# Shield_r0.net
KiCad netlist of a schematic drawn in EAGLE
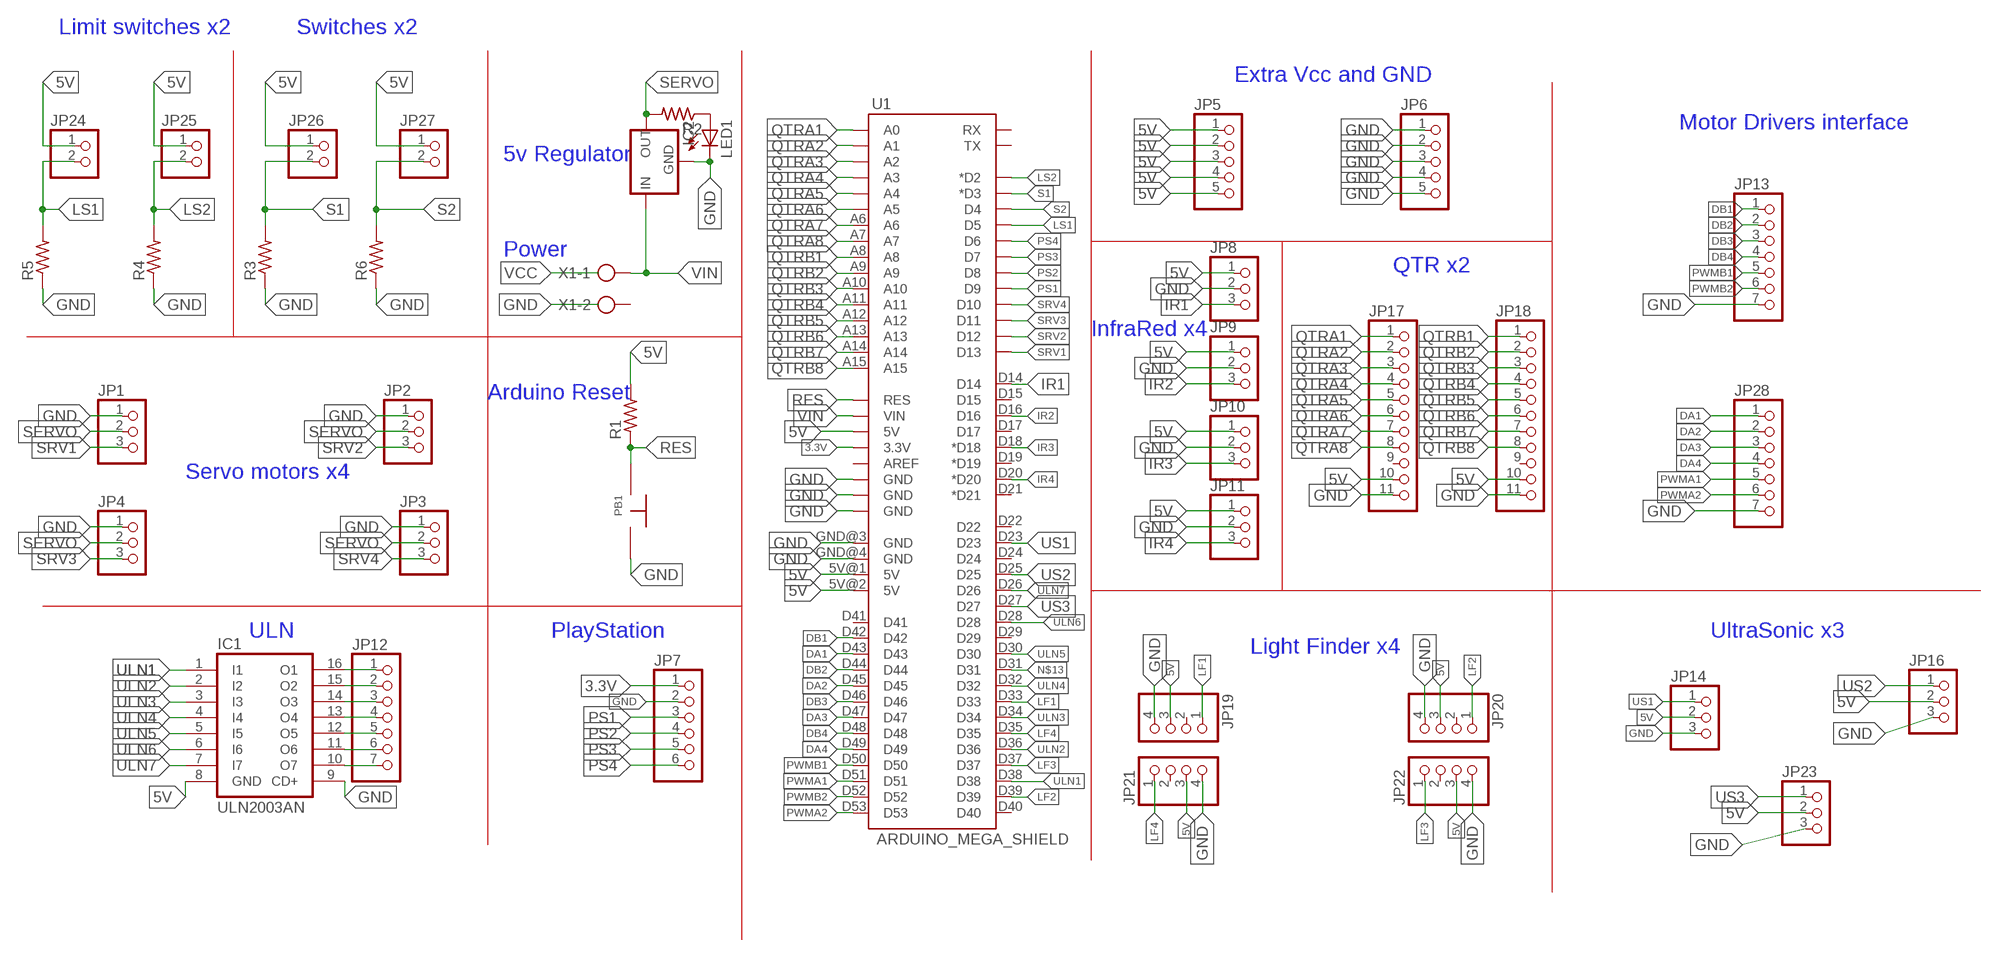
[diagram p0: schematic, sheet 1]

(export (version "E")
  (design (tool "Eeschema 10.0.6"))
  (components
    (comp (ref "IC1")
      (value "ULN2003AN")
      (footprint "eagle-import:DIL16")
      (libsource (lib "eagle-import") (part "ULN2003AN"))
    )
    (comp (ref "IC2")
      (value "78XXS")
      (footprint "eagle-import:78XXS")
      (libsource (lib "eagle-import") (part "78XXS"))
    )
    (comp (ref "JP1")
      (value "PINHD-1X3")
      (footprint "eagle-import:1X03")
      (libsource (lib "eagle-import") (part "PINHD-1X3"))
    )
    (comp (ref "JP2")
      (value "PINHD-1X3")
      (footprint "eagle-import:1X03")
      (libsource (lib "eagle-import") (part "PINHD-1X3"))
    )
    (comp (ref "JP3")
      (value "PINHD-1X3")
      (footprint "eagle-import:1X03")
      (libsource (lib "eagle-import") (part "PINHD-1X3"))
    )
    (comp (ref "JP4")
      (value "PINHD-1X3")
      (footprint "eagle-import:1X03")
      (libsource (lib "eagle-import") (part "PINHD-1X3"))
    )
    (comp (ref "JP5")
      (value "PINHD-1X5")
      (footprint "eagle-import:1X05")
      (libsource (lib "eagle-import") (part "PINHD-1X5"))
    )
    (comp (ref "JP6")
      (value "PINHD-1X5")
      (footprint "eagle-import:1X05")
      (libsource (lib "eagle-import") (part "PINHD-1X5"))
    )
    (comp (ref "JP7")
      (value "PINHD-1X6")
      (footprint "eagle-import:1X06")
      (libsource (lib "eagle-import") (part "PINHD-1X6"))
    )
    (comp (ref "JP8")
      (value "PINHD-1X3")
      (footprint "eagle-import:1X03")
      (libsource (lib "eagle-import") (part "PINHD-1X3"))
    )
    (comp (ref "JP9")
      (value "PINHD-1X3")
      (footprint "eagle-import:1X03")
      (libsource (lib "eagle-import") (part "PINHD-1X3"))
    )
    (comp (ref "JP10")
      (value "PINHD-1X3")
      (footprint "eagle-import:1X03")
      (libsource (lib "eagle-import") (part "PINHD-1X3"))
    )
    (comp (ref "JP11")
      (value "PINHD-1X3")
      (footprint "eagle-import:1X03")
      (libsource (lib "eagle-import") (part "PINHD-1X3"))
    )
    (comp (ref "JP12")
      (value "PINHD-1X7")
      (footprint "eagle-import:1X07")
      (libsource (lib "eagle-import") (part "PINHD-1X7"))
    )
    (comp (ref "JP13")
      (value "PINHD-1X7")
      (footprint "eagle-import:1X07")
      (libsource (lib "eagle-import") (part "PINHD-1X7"))
    )
    (comp (ref "JP14")
      (value "PINHD-1X3")
      (footprint "eagle-import:1X03")
      (libsource (lib "eagle-import") (part "PINHD-1X3"))
    )
    (comp (ref "JP16")
      (value "PINHD-1X3")
      (footprint "eagle-import:1X03")
      (libsource (lib "eagle-import") (part "PINHD-1X3"))
    )
    (comp (ref "JP17")
      (value "PINHD-1X11")
      (footprint "eagle-import:1X11")
      (libsource (lib "eagle-import") (part "PINHD-1X11"))
    )
    (comp (ref "JP18")
      (value "PINHD-1X11")
      (footprint "eagle-import:1X11")
      (libsource (lib "eagle-import") (part "PINHD-1X11"))
    )
    (comp (ref "JP19")
      (value "PINHD-1X4")
      (footprint "eagle-import:1X04")
      (libsource (lib "eagle-import") (part "PINHD-1X4"))
    )
    (comp (ref "JP20")
      (value "PINHD-1X4")
      (footprint "eagle-import:1X04")
      (libsource (lib "eagle-import") (part "PINHD-1X4"))
    )
    (comp (ref "JP21")
      (value "PINHD-1X4")
      (footprint "eagle-import:1X04")
      (libsource (lib "eagle-import") (part "PINHD-1X4"))
    )
    (comp (ref "JP22")
      (value "PINHD-1X4")
      (footprint "eagle-import:1X04")
      (libsource (lib "eagle-import") (part "PINHD-1X4"))
    )
    (comp (ref "JP23")
      (value "PINHD-1X3")
      (footprint "eagle-import:1X03")
      (libsource (lib "eagle-import") (part "PINHD-1X3"))
    )
    (comp (ref "JP24")
      (value "PINHD-1X2")
      (footprint "eagle-import:1X02")
      (libsource (lib "eagle-import") (part "PINHD-1X2"))
    )
    (comp (ref "JP25")
      (value "PINHD-1X2")
      (footprint "eagle-import:1X02")
      (libsource (lib "eagle-import") (part "PINHD-1X2"))
    )
    (comp (ref "JP26")
      (value "PINHD-1X2")
      (footprint "eagle-import:1X02")
      (libsource (lib "eagle-import") (part "PINHD-1X2"))
    )
    (comp (ref "JP27")
      (value "PINHD-1X2")
      (footprint "eagle-import:1X02")
      (libsource (lib "eagle-import") (part "PINHD-1X2"))
    )
    (comp (ref "JP28")
      (value "PINHD-1X7")
      (footprint "eagle-import:1X07")
      (libsource (lib "eagle-import") (part "PINHD-1X7"))
    )
    (comp (ref "LED1")
      (value "LED5MM")
      (footprint "eagle-import:LED5MM")
      (libsource (lib "eagle-import") (part "LED5MM"))
    )
    (comp (ref "PB1")
      (value "PUSH")
      (footprint "eagle-import:PUSHBUTTON")
      (libsource (lib "eagle-import") (part "PUSH"))
    )
    (comp (ref "R1")
      (value "R-US_0207/10")
      (footprint "eagle-import:0207_10")
      (libsource (lib "eagle-import") (part "R-US_0207/10"))
    )
    (comp (ref "R2")
      (value "R-US_0207/10")
      (footprint "eagle-import:0207_10")
      (libsource (lib "eagle-import") (part "R-US_0207/10"))
    )
    (comp (ref "R3")
      (value "R-US_0207/10")
      (footprint "eagle-import:0207_10")
      (libsource (lib "eagle-import") (part "R-US_0207/10"))
    )
    (comp (ref "R4")
      (value "R-US_0207/10")
      (footprint "eagle-import:0207_10")
      (libsource (lib "eagle-import") (part "R-US_0207/10"))
    )
    (comp (ref "R5")
      (value "R-US_0207/10")
      (footprint "eagle-import:0207_10")
      (libsource (lib "eagle-import") (part "R-US_0207/10"))
    )
    (comp (ref "R6")
      (value "R-US_0207/10")
      (footprint "eagle-import:0207_10")
      (libsource (lib "eagle-import") (part "R-US_0207/10"))
    )
    (comp (ref "U1")
      (value "ARDUINO_MEGA_SHIELD")
      (footprint "eagle-import:ARDUINO_MEGA_SHIELD")
      (libsource (lib "eagle-import") (part "ARDUINO_MEGA_SHIELD"))
    )
    (comp (ref "X1")
      (value "AK500/2-H")
      (footprint "eagle-import:AK500_2-H")
      (libsource (lib "eagle-import") (part "AK500/2-H"))
    )
  )
  (nets
    (net (code "1") (name "3.3V") (class "Default")
      (node (ref "JP7") (pin "1") (pinfunction "1_1") (pintype "passive"))
      (node (ref "U1") (pin "3.3V") (pinfunction "3.3V_3.3V") (pintype "bidirectional"))
    )
    (net (code "2") (name "5V") (class "Default")
      (node (ref "IC1") (pin "8") (pinfunction "GND_8") (pintype "power_in"))
      (node (ref "JP10") (pin "1") (pinfunction "1_1") (pintype "passive"))
      (node (ref "JP11") (pin "1") (pinfunction "1_1") (pintype "passive"))
      (node (ref "JP14") (pin "2") (pinfunction "2_2") (pintype "passive"))
      (node (ref "JP16") (pin "2") (pinfunction "2_2") (pintype "passive"))
      (node (ref "JP17") (pin "10") (pinfunction "10_10") (pintype "passive"))
      (node (ref "JP18") (pin "10") (pinfunction "10_10") (pintype "passive"))
      (node (ref "JP19") (pin "3") (pinfunction "3_3") (pintype "passive"))
      (node (ref "JP20") (pin "3") (pinfunction "3_3") (pintype "passive"))
      (node (ref "JP21") (pin "3") (pinfunction "3_3") (pintype "passive"))
      (node (ref "JP22") (pin "3") (pinfunction "3_3") (pintype "passive"))
      (node (ref "JP23") (pin "2") (pinfunction "2_2") (pintype "passive"))
      (node (ref "JP24") (pin "1") (pinfunction "1_1") (pintype "passive"))
      (node (ref "JP25") (pin "1") (pinfunction "1_1") (pintype "passive"))
      (node (ref "JP26") (pin "1") (pinfunction "1_1") (pintype "passive"))
      (node (ref "JP27") (pin "1") (pinfunction "1_1") (pintype "passive"))
      (node (ref "JP5") (pin "1") (pinfunction "1_1") (pintype "passive"))
      (node (ref "JP5") (pin "2") (pinfunction "2_2") (pintype "passive"))
      (node (ref "JP5") (pin "3") (pinfunction "3_3") (pintype "passive"))
      (node (ref "JP5") (pin "4") (pinfunction "4_4") (pintype "passive"))
      (node (ref "JP5") (pin "5") (pinfunction "5_5") (pintype "passive"))
      (node (ref "JP8") (pin "1") (pinfunction "1_1") (pintype "passive"))
      (node (ref "JP9") (pin "1") (pinfunction "1_1") (pintype "passive"))
      (node (ref "R1") (pin "2") (pinfunction "2_2") (pintype "passive"))
      (node (ref "U1") (pin "5V@0") (pinfunction "5V_5V@0") (pintype "power_in"))
      (node (ref "U1") (pin "5V@1") (pinfunction "5V_5V@1") (pintype "power_in"))
      (node (ref "U1") (pin "5V@2") (pinfunction "5V_5V@2") (pintype "power_in"))
    )
    (net (code "3") (name "DA1") (class "Default")
      (node (ref "JP28") (pin "1") (pinfunction "1_1") (pintype "passive"))
      (node (ref "U1") (pin "D43") (pinfunction "D43_D43") (pintype "bidirectional"))
    )
    (net (code "4") (name "DA2") (class "Default")
      (node (ref "JP28") (pin "2") (pinfunction "2_2") (pintype "passive"))
      (node (ref "U1") (pin "D45") (pinfunction "D45_D45") (pintype "bidirectional"))
    )
    (net (code "5") (name "DA3") (class "Default")
      (node (ref "JP28") (pin "3") (pinfunction "3_3") (pintype "passive"))
      (node (ref "U1") (pin "D47") (pinfunction "D47_D47") (pintype "bidirectional"))
    )
    (net (code "6") (name "DA4") (class "Default")
      (node (ref "JP28") (pin "4") (pinfunction "4_4") (pintype "passive"))
      (node (ref "U1") (pin "D49") (pinfunction "D49_D49") (pintype "bidirectional"))
    )
    (net (code "7") (name "DB1") (class "Default")
      (node (ref "JP13") (pin "1") (pinfunction "1_1") (pintype "passive"))
      (node (ref "U1") (pin "D42") (pinfunction "D42_D42") (pintype "bidirectional"))
    )
    (net (code "8") (name "DB2") (class "Default")
      (node (ref "JP13") (pin "2") (pinfunction "2_2") (pintype "passive"))
      (node (ref "U1") (pin "D44") (pinfunction "D44_D44") (pintype "bidirectional"))
    )
    (net (code "9") (name "DB3") (class "Default")
      (node (ref "JP13") (pin "3") (pinfunction "3_3") (pintype "passive"))
      (node (ref "U1") (pin "D46") (pinfunction "D46_D46") (pintype "bidirectional"))
    )
    (net (code "10") (name "DB4") (class "Default")
      (node (ref "JP13") (pin "4") (pinfunction "4_4") (pintype "passive"))
      (node (ref "U1") (pin "D48") (pinfunction "D48_D48") (pintype "bidirectional"))
    )
    (net (code "11") (name "GND") (class "Default")
      (node (ref "IC1") (pin "9") (pinfunction "CD+_9") (pintype "passive"))
      (node (ref "IC2") (pin "GND") (pinfunction "GND_GND") (pintype "input"))
      (node (ref "JP1") (pin "1") (pinfunction "1_1") (pintype "passive"))
      (node (ref "JP10") (pin "2") (pinfunction "2_2") (pintype "passive"))
      (node (ref "JP11") (pin "2") (pinfunction "2_2") (pintype "passive"))
      (node (ref "JP13") (pin "7") (pinfunction "7_7") (pintype "passive"))
      (node (ref "JP14") (pin "3") (pinfunction "3_3") (pintype "passive"))
      (node (ref "JP16") (pin "3") (pinfunction "3_3") (pintype "passive"))
      (node (ref "JP17") (pin "11") (pinfunction "11_11") (pintype "passive"))
      (node (ref "JP18") (pin "11") (pinfunction "11_11") (pintype "passive"))
      (node (ref "JP19") (pin "4") (pinfunction "4_4") (pintype "passive"))
      (node (ref "JP2") (pin "1") (pinfunction "1_1") (pintype "passive"))
      (node (ref "JP20") (pin "4") (pinfunction "4_4") (pintype "passive"))
      (node (ref "JP21") (pin "4") (pinfunction "4_4") (pintype "passive"))
      (node (ref "JP22") (pin "4") (pinfunction "4_4") (pintype "passive"))
      (node (ref "JP23") (pin "3") (pinfunction "3_3") (pintype "passive"))
      (node (ref "JP28") (pin "7") (pinfunction "7_7") (pintype "passive"))
      (node (ref "JP3") (pin "1") (pinfunction "1_1") (pintype "passive"))
      (node (ref "JP4") (pin "1") (pinfunction "1_1") (pintype "passive"))
      (node (ref "JP6") (pin "1") (pinfunction "1_1") (pintype "passive"))
      (node (ref "JP6") (pin "2") (pinfunction "2_2") (pintype "passive"))
      (node (ref "JP6") (pin "3") (pinfunction "3_3") (pintype "passive"))
      (node (ref "JP6") (pin "4") (pinfunction "4_4") (pintype "passive"))
      (node (ref "JP6") (pin "5") (pinfunction "5_5") (pintype "passive"))
      (node (ref "JP7") (pin "2") (pinfunction "2_2") (pintype "passive"))
      (node (ref "JP8") (pin "2") (pinfunction "2_2") (pintype "passive"))
      (node (ref "JP9") (pin "2") (pinfunction "2_2") (pintype "passive"))
      (node (ref "LED1") (pin "K") (pinfunction "C_K") (pintype "passive"))
      (node (ref "PB1") (pin "P$2") (pinfunction "3_P$2") (pintype "bidirectional"))
      (node (ref "R3") (pin "1") (pinfunction "1_1") (pintype "passive"))
      (node (ref "R4") (pin "1") (pinfunction "1_1") (pintype "passive"))
      (node (ref "R5") (pin "1") (pinfunction "1_1") (pintype "passive"))
      (node (ref "R6") (pin "1") (pinfunction "1_1") (pintype "passive"))
      (node (ref "U1") (pin "GND@0") (pinfunction "GND_GND@0") (pintype "power_in"))
      (node (ref "U1") (pin "GND@1") (pinfunction "GND_GND@1") (pintype "power_in"))
      (node (ref "U1") (pin "GND@2") (pinfunction "GND_GND@2") (pintype "power_in"))
      (node (ref "U1") (pin "GND@3") (pinfunction "GND_GND@3") (pintype "power_in"))
      (node (ref "U1") (pin "GND@4") (pinfunction "GND_GND@4") (pintype "power_in"))
    )
    (net (code "12") (name "IR1") (class "Default")
      (node (ref "JP8") (pin "3") (pinfunction "3_3") (pintype "passive"))
      (node (ref "U1") (pin "D14") (pinfunction "D14_D14") (pintype "bidirectional"))
    )
    (net (code "13") (name "IR2") (class "Default")
      (node (ref "JP9") (pin "3") (pinfunction "3_3") (pintype "passive"))
      (node (ref "U1") (pin "D16") (pinfunction "D16_D16") (pintype "bidirectional"))
    )
    (net (code "14") (name "IR3") (class "Default")
      (node (ref "JP10") (pin "3") (pinfunction "3_3") (pintype "passive"))
      (node (ref "U1") (pin "D18") (pinfunction "*D18_D18") (pintype "bidirectional"))
    )
    (net (code "15") (name "IR4") (class "Default")
      (node (ref "JP11") (pin "3") (pinfunction "3_3") (pintype "passive"))
      (node (ref "U1") (pin "D20") (pinfunction "*D20_D20") (pintype "bidirectional"))
    )
    (net (code "16") (name "LF1") (class "Default")
      (node (ref "JP19") (pin "1") (pinfunction "1_1") (pintype "passive"))
      (node (ref "U1") (pin "D33") (pinfunction "D33_D33") (pintype "bidirectional"))
    )
    (net (code "17") (name "LF2") (class "Default")
      (node (ref "JP20") (pin "1") (pinfunction "1_1") (pintype "passive"))
      (node (ref "U1") (pin "D39") (pinfunction "D39_D39") (pintype "bidirectional"))
    )
    (net (code "18") (name "LF3") (class "Default")
      (node (ref "JP22") (pin "1") (pinfunction "1_1") (pintype "passive"))
      (node (ref "U1") (pin "D37") (pinfunction "D37_D37") (pintype "bidirectional"))
    )
    (net (code "19") (name "LF4") (class "Default")
      (node (ref "JP21") (pin "1") (pinfunction "1_1") (pintype "passive"))
      (node (ref "U1") (pin "D35") (pinfunction "D35_D35") (pintype "bidirectional"))
    )
    (net (code "20") (name "LS1") (class "Default")
      (node (ref "JP24") (pin "2") (pinfunction "2_2") (pintype "passive"))
      (node (ref "R5") (pin "2") (pinfunction "2_2") (pintype "passive"))
      (node (ref "U1") (pin "D5") (pinfunction "D5_D5") (pintype "bidirectional"))
    )
    (net (code "21") (name "LS2") (class "Default")
      (node (ref "JP25") (pin "2") (pinfunction "2_2") (pintype "passive"))
      (node (ref "R4") (pin "2") (pinfunction "2_2") (pintype "passive"))
      (node (ref "U1") (pin "D2") (pinfunction "*D2_D2") (pintype "bidirectional"))
    )
    (net (code "22") (name "N$13") (class "Default")
      (node (ref "U1") (pin "D31") (pinfunction "D31_D31") (pintype "bidirectional"))
    )
    (net (code "23") (name "Net-(IC1-O1)") (class "Default")
      (node (ref "IC1") (pin "16") (pinfunction "O1_16") (pintype "open_collector"))
      (node (ref "JP12") (pin "1") (pinfunction "1_1") (pintype "passive"))
    )
    (net (code "24") (name "Net-(IC1-O2)") (class "Default")
      (node (ref "IC1") (pin "15") (pinfunction "O2_15") (pintype "open_collector"))
      (node (ref "JP12") (pin "2") (pinfunction "2_2") (pintype "passive"))
    )
    (net (code "25") (name "Net-(IC1-O3)") (class "Default")
      (node (ref "IC1") (pin "14") (pinfunction "O3_14") (pintype "open_collector"))
      (node (ref "JP12") (pin "3") (pinfunction "3_3") (pintype "passive"))
    )
    (net (code "26") (name "Net-(IC1-O4)") (class "Default")
      (node (ref "IC1") (pin "13") (pinfunction "O4_13") (pintype "open_collector"))
      (node (ref "JP12") (pin "4") (pinfunction "4_4") (pintype "passive"))
    )
    (net (code "27") (name "Net-(IC1-O5)") (class "Default")
      (node (ref "IC1") (pin "12") (pinfunction "O5_12") (pintype "open_collector"))
      (node (ref "JP12") (pin "5") (pinfunction "5_5") (pintype "passive"))
    )
    (net (code "28") (name "Net-(IC1-O6)") (class "Default")
      (node (ref "IC1") (pin "11") (pinfunction "O6_11") (pintype "open_collector"))
      (node (ref "JP12") (pin "6") (pinfunction "6_6") (pintype "passive"))
    )
    (net (code "29") (name "Net-(IC1-O7)") (class "Default")
      (node (ref "IC1") (pin "10") (pinfunction "O7_10") (pintype "open_collector"))
      (node (ref "JP12") (pin "7") (pinfunction "7_7") (pintype "passive"))
    )
    (net (code "30") (name "Net-(LED1-PadA)") (class "Default")
      (node (ref "LED1") (pin "A") (pinfunction "A_A") (pintype "passive"))
      (node (ref "R2") (pin "1") (pinfunction "1_1") (pintype "passive"))
    )
    (net (code "31") (name "PS1") (class "Default")
      (node (ref "JP7") (pin "3") (pinfunction "3_3") (pintype "passive"))
      (node (ref "U1") (pin "D9") (pinfunction "D9_D9") (pintype "bidirectional"))
    )
    (net (code "32") (name "PS2") (class "Default")
      (node (ref "JP7") (pin "4") (pinfunction "4_4") (pintype "passive"))
      (node (ref "U1") (pin "D8") (pinfunction "D8_D8") (pintype "bidirectional"))
    )
    (net (code "33") (name "PS3") (class "Default")
      (node (ref "JP7") (pin "5") (pinfunction "5_5") (pintype "passive"))
      (node (ref "U1") (pin "D7") (pinfunction "D7_D7") (pintype "bidirectional"))
    )
    (net (code "34") (name "PS4") (class "Default")
      (node (ref "JP7") (pin "6") (pinfunction "6_6") (pintype "passive"))
      (node (ref "U1") (pin "D6") (pinfunction "D6_D6") (pintype "bidirectional"))
    )
    (net (code "35") (name "PWMA1") (class "Default")
      (node (ref "JP28") (pin "5") (pinfunction "5_5") (pintype "passive"))
      (node (ref "U1") (pin "D51") (pinfunction "D51_D51") (pintype "bidirectional"))
    )
    (net (code "36") (name "PWMA2") (class "Default")
      (node (ref "JP28") (pin "6") (pinfunction "6_6") (pintype "passive"))
      (node (ref "U1") (pin "D53") (pinfunction "D53_D53") (pintype "bidirectional"))
    )
    (net (code "37") (name "PWMB1") (class "Default")
      (node (ref "JP13") (pin "5") (pinfunction "5_5") (pintype "passive"))
      (node (ref "U1") (pin "D50") (pinfunction "D50_D50") (pintype "bidirectional"))
    )
    (net (code "38") (name "PWMB2") (class "Default")
      (node (ref "JP13") (pin "6") (pinfunction "6_6") (pintype "passive"))
      (node (ref "U1") (pin "D52") (pinfunction "D52_D52") (pintype "bidirectional"))
    )
    (net (code "39") (name "QTRA1") (class "Default")
      (node (ref "JP17") (pin "1") (pinfunction "1_1") (pintype "passive"))
      (node (ref "U1") (pin "A0") (pinfunction "A0_A0") (pintype "bidirectional"))
    )
    (net (code "40") (name "QTRA2") (class "Default")
      (node (ref "JP17") (pin "2") (pinfunction "2_2") (pintype "passive"))
      (node (ref "U1") (pin "A1") (pinfunction "A1_A1") (pintype "bidirectional"))
    )
    (net (code "41") (name "QTRA3") (class "Default")
      (node (ref "JP17") (pin "3") (pinfunction "3_3") (pintype "passive"))
      (node (ref "U1") (pin "A2") (pinfunction "A2_A2") (pintype "bidirectional"))
    )
    (net (code "42") (name "QTRA4") (class "Default")
      (node (ref "JP17") (pin "4") (pinfunction "4_4") (pintype "passive"))
      (node (ref "U1") (pin "A3") (pinfunction "A3_A3") (pintype "bidirectional"))
    )
    (net (code "43") (name "QTRA5") (class "Default")
      (node (ref "JP17") (pin "5") (pinfunction "5_5") (pintype "passive"))
      (node (ref "U1") (pin "A4") (pinfunction "A4_A4") (pintype "bidirectional"))
    )
    (net (code "44") (name "QTRA6") (class "Default")
      (node (ref "JP17") (pin "6") (pinfunction "6_6") (pintype "passive"))
      (node (ref "U1") (pin "A5") (pinfunction "A5_A5") (pintype "bidirectional"))
    )
    (net (code "45") (name "QTRA7") (class "Default")
      (node (ref "JP17") (pin "7") (pinfunction "7_7") (pintype "passive"))
      (node (ref "U1") (pin "A6") (pinfunction "A6_A6") (pintype "bidirectional"))
    )
    (net (code "46") (name "QTRA8") (class "Default")
      (node (ref "JP17") (pin "8") (pinfunction "8_8") (pintype "passive"))
      (node (ref "U1") (pin "A7") (pinfunction "A7_A7") (pintype "bidirectional"))
    )
    (net (code "47") (name "QTRB1") (class "Default")
      (node (ref "JP18") (pin "1") (pinfunction "1_1") (pintype "passive"))
      (node (ref "U1") (pin "A8") (pinfunction "A8_A8") (pintype "bidirectional"))
    )
    (net (code "48") (name "QTRB2") (class "Default")
      (node (ref "JP18") (pin "2") (pinfunction "2_2") (pintype "passive"))
      (node (ref "U1") (pin "A9") (pinfunction "A9_A9") (pintype "bidirectional"))
    )
    (net (code "49") (name "QTRB3") (class "Default")
      (node (ref "JP18") (pin "3") (pinfunction "3_3") (pintype "passive"))
      (node (ref "U1") (pin "A10") (pinfunction "A10_A10") (pintype "bidirectional"))
    )
    (net (code "50") (name "QTRB4") (class "Default")
      (node (ref "JP18") (pin "4") (pinfunction "4_4") (pintype "passive"))
      (node (ref "U1") (pin "A11") (pinfunction "A11_A11") (pintype "bidirectional"))
    )
    (net (code "51") (name "QTRB5") (class "Default")
      (node (ref "JP18") (pin "5") (pinfunction "5_5") (pintype "passive"))
      (node (ref "U1") (pin "A12") (pinfunction "A12_A12") (pintype "bidirectional"))
    )
    (net (code "52") (name "QTRB6") (class "Default")
      (node (ref "JP18") (pin "6") (pinfunction "6_6") (pintype "passive"))
      (node (ref "U1") (pin "A13") (pinfunction "A13_A13") (pintype "bidirectional"))
    )
    (net (code "53") (name "QTRB7") (class "Default")
      (node (ref "JP18") (pin "7") (pinfunction "7_7") (pintype "passive"))
      (node (ref "U1") (pin "A14") (pinfunction "A14_A14") (pintype "bidirectional"))
    )
    (net (code "54") (name "QTRB8") (class "Default")
      (node (ref "JP18") (pin "8") (pinfunction "8_8") (pintype "passive"))
      (node (ref "U1") (pin "A15") (pinfunction "A15_A15") (pintype "bidirectional"))
    )
    (net (code "55") (name "RES") (class "Default")
      (node (ref "PB1") (pin "P$1") (pinfunction "2_P$1") (pintype "bidirectional"))
      (node (ref "R1") (pin "1") (pinfunction "1_1") (pintype "passive"))
      (node (ref "U1") (pin "RES") (pinfunction "RES_RES") (pintype "bidirectional"))
    )
    (net (code "56") (name "S1") (class "Default")
      (node (ref "JP26") (pin "2") (pinfunction "2_2") (pintype "passive"))
      (node (ref "R3") (pin "2") (pinfunction "2_2") (pintype "passive"))
      (node (ref "U1") (pin "D3") (pinfunction "*D3_D3") (pintype "bidirectional"))
    )
    (net (code "57") (name "S2") (class "Default")
      (node (ref "JP27") (pin "2") (pinfunction "2_2") (pintype "passive"))
      (node (ref "R6") (pin "2") (pinfunction "2_2") (pintype "passive"))
      (node (ref "U1") (pin "D4") (pinfunction "D4_D4") (pintype "bidirectional"))
    )
    (net (code "58") (name "SERVO") (class "Default")
      (node (ref "IC2") (pin "OUT") (pinfunction "OUT_OUT") (pintype "passive"))
      (node (ref "JP1") (pin "2") (pinfunction "2_2") (pintype "passive"))
      (node (ref "JP2") (pin "2") (pinfunction "2_2") (pintype "passive"))
      (node (ref "JP3") (pin "2") (pinfunction "2_2") (pintype "passive"))
      (node (ref "JP4") (pin "2") (pinfunction "2_2") (pintype "passive"))
      (node (ref "R2") (pin "2") (pinfunction "2_2") (pintype "passive"))
    )
    (net (code "59") (name "SRV1") (class "Default")
      (node (ref "JP1") (pin "3") (pinfunction "3_3") (pintype "passive"))
      (node (ref "U1") (pin "D13") (pinfunction "D13_D13") (pintype "bidirectional"))
    )
    (net (code "60") (name "SRV2") (class "Default")
      (node (ref "JP2") (pin "3") (pinfunction "3_3") (pintype "passive"))
      (node (ref "U1") (pin "D12") (pinfunction "D12_D12") (pintype "bidirectional"))
    )
    (net (code "61") (name "SRV3") (class "Default")
      (node (ref "JP4") (pin "3") (pinfunction "3_3") (pintype "passive"))
      (node (ref "U1") (pin "D11") (pinfunction "D11_D11") (pintype "bidirectional"))
    )
    (net (code "62") (name "SRV4") (class "Default")
      (node (ref "JP3") (pin "3") (pinfunction "3_3") (pintype "passive"))
      (node (ref "U1") (pin "D10") (pinfunction "D10_D10") (pintype "bidirectional"))
    )
    (net (code "63") (name "ULN1") (class "Default")
      (node (ref "IC1") (pin "1") (pinfunction "I1_1") (pintype "input"))
      (node (ref "U1") (pin "D38") (pinfunction "D38_D38") (pintype "bidirectional"))
    )
    (net (code "64") (name "ULN2") (class "Default")
      (node (ref "IC1") (pin "2") (pinfunction "I2_2") (pintype "input"))
      (node (ref "U1") (pin "D36") (pinfunction "D36_D36") (pintype "bidirectional"))
    )
    (net (code "65") (name "ULN3") (class "Default")
      (node (ref "IC1") (pin "3") (pinfunction "I3_3") (pintype "input"))
      (node (ref "U1") (pin "D34") (pinfunction "D34_D34") (pintype "bidirectional"))
    )
    (net (code "66") (name "ULN4") (class "Default")
      (node (ref "IC1") (pin "4") (pinfunction "I4_4") (pintype "input"))
      (node (ref "U1") (pin "D32") (pinfunction "D32_D32") (pintype "bidirectional"))
    )
    (net (code "67") (name "ULN5") (class "Default")
      (node (ref "IC1") (pin "5") (pinfunction "I5_5") (pintype "input"))
      (node (ref "U1") (pin "D30") (pinfunction "D30_D30") (pintype "bidirectional"))
    )
    (net (code "68") (name "ULN6") (class "Default")
      (node (ref "IC1") (pin "6") (pinfunction "I6_6") (pintype "input"))
      (node (ref "U1") (pin "D28") (pinfunction "D28_D28") (pintype "bidirectional"))
    )
    (net (code "69") (name "ULN7") (class "Default")
      (node (ref "IC1") (pin "7") (pinfunction "I7_7") (pintype "input"))
      (node (ref "U1") (pin "D26") (pinfunction "D26_D26") (pintype "bidirectional"))
    )
    (net (code "70") (name "US1") (class "Default")
      (node (ref "JP14") (pin "1") (pinfunction "1_1") (pintype "passive"))
      (node (ref "U1") (pin "D23") (pinfunction "D23_D23") (pintype "bidirectional"))
    )
    (net (code "71") (name "US2") (class "Default")
      (node (ref "JP16") (pin "1") (pinfunction "1_1") (pintype "passive"))
      (node (ref "U1") (pin "D25") (pinfunction "D25_D25") (pintype "bidirectional"))
    )
    (net (code "72") (name "US3") (class "Default")
      (node (ref "JP23") (pin "1") (pinfunction "1_1") (pintype "passive"))
      (node (ref "U1") (pin "D27") (pinfunction "D27_D27") (pintype "bidirectional"))
    )
    (net (code "74") (name "VIN") (class "Default")
      (node (ref "IC2") (pin "IN") (pinfunction "IN_IN") (pintype "input"))
      (node (ref "U1") (pin "VIN") (pinfunction "VIN_VIN") (pintype "bidirectional"))
      (node (ref "X1") (pin "1") (pinfunction "KL_1") (pintype "passive"))
    )
    (net (code "75") (name "unconnected-(JP17-Pad9)") (class "Default")
      (node (ref "JP17") (pin "9") (pinfunction "9_9") (pintype "passive"))
    )
    (net (code "76") (name "unconnected-(JP18-Pad9)") (class "Default")
      (node (ref "JP18") (pin "9") (pinfunction "9_9") (pintype "passive"))
    )
    (net (code "77") (name "unconnected-(JP19-Pad2)") (class "Default")
      (node (ref "JP19") (pin "2") (pinfunction "2_2") (pintype "passive"))
    )
    (net (code "78") (name "unconnected-(JP20-Pad2)") (class "Default")
      (node (ref "JP20") (pin "2") (pinfunction "2_2") (pintype "passive"))
    )
    (net (code "79") (name "unconnected-(JP21-Pad2)") (class "Default")
      (node (ref "JP21") (pin "2") (pinfunction "2_2") (pintype "passive"))
    )
    (net (code "80") (name "unconnected-(JP22-Pad2)") (class "Default")
      (node (ref "JP22") (pin "2") (pinfunction "2_2") (pintype "passive"))
    )
    (net (code "81") (name "unconnected-(U1-*D19-PadD19)") (class "Default")
      (node (ref "U1") (pin "D19") (pinfunction "*D19_D19") (pintype "bidirectional"))
    )
    (net (code "82") (name "unconnected-(U1-*D21-PadD21)") (class "Default")
      (node (ref "U1") (pin "D21") (pinfunction "*D21_D21") (pintype "bidirectional"))
    )
    (net (code "83") (name "unconnected-(U1-PadAREF)") (class "Default")
      (node (ref "U1") (pin "AREF") (pinfunction "AREF_AREF") (pintype "bidirectional"))
    )
    (net (code "84") (name "unconnected-(U1-PadD15)") (class "Default")
      (node (ref "U1") (pin "D15") (pinfunction "D15_D15") (pintype "bidirectional"))
    )
    (net (code "85") (name "unconnected-(U1-PadD17)") (class "Default")
      (node (ref "U1") (pin "D17") (pinfunction "D17_D17") (pintype "bidirectional"))
    )
    (net (code "86") (name "unconnected-(U1-PadD22)") (class "Default")
      (node (ref "U1") (pin "D22") (pinfunction "D22_D22") (pintype "bidirectional"))
    )
    (net (code "87") (name "unconnected-(U1-PadD24)") (class "Default")
      (node (ref "U1") (pin "D24") (pinfunction "D24_D24") (pintype "bidirectional"))
    )
    (net (code "88") (name "unconnected-(U1-PadD29)") (class "Default")
      (node (ref "U1") (pin "D29") (pinfunction "D29_D29") (pintype "bidirectional"))
    )
    (net (code "89") (name "unconnected-(U1-PadD40)") (class "Default")
      (node (ref "U1") (pin "D40") (pinfunction "D40_D40") (pintype "bidirectional"))
    )
    (net (code "90") (name "unconnected-(U1-PadD41)") (class "Default")
      (node (ref "U1") (pin "D41") (pinfunction "D41_D41") (pintype "bidirectional"))
    )
    (net (code "91") (name "unconnected-(U1-PadRX)") (class "Default")
      (node (ref "U1") (pin "RX") (pinfunction "RX_RX") (pintype "bidirectional"))
    )
    (net (code "92") (name "unconnected-(U1-PadTX)") (class "Default")
      (node (ref "U1") (pin "TX") (pinfunction "TX_TX") (pintype "bidirectional"))
    )
    (net (code "93") (name "unconnected-(X1B-KL-Pad2)") (class "Default")
      (node (ref "X1") (pin "2") (pinfunction "KL_2") (pintype "passive"))
    )
  )
)
